# Adafruit_Feather_nRF52840_Sense.net
KiCad netlist of a schematic drawn in EAGLE
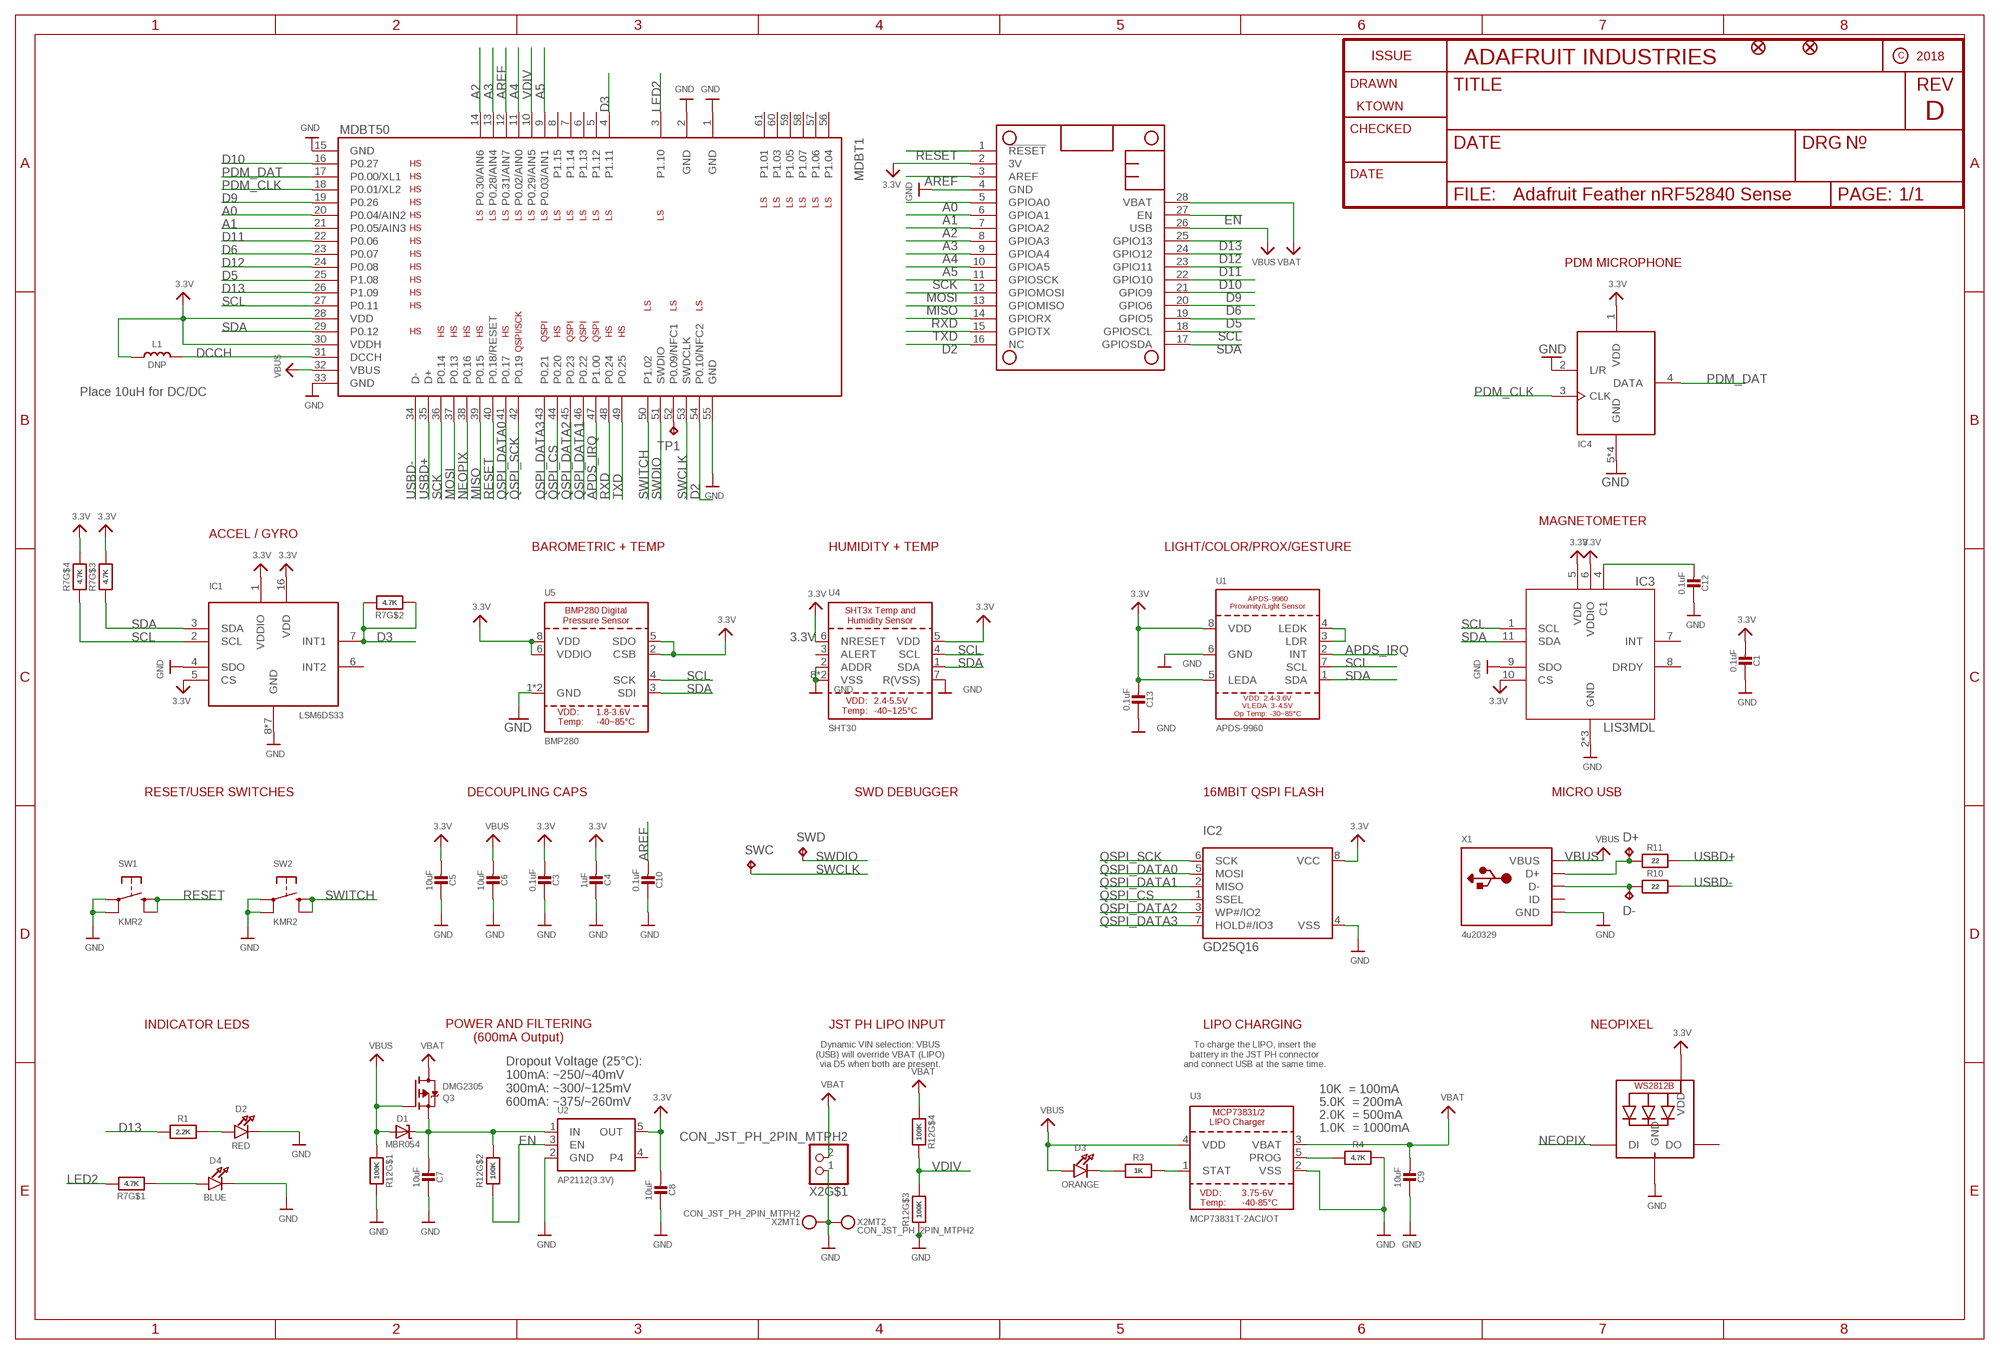
[diagram p0: schematic, sheet 1]

(export (version "E")
  (design (tool "Eeschema 10.0.6"))
  (components
    (comp (ref "C1")
      (value "0.1uF")
      (footprint "eagle-import:0603-NO")
      (libsource (lib "eagle-import") (part "CAP_CERAMIC0603_NO"))
    )
    (comp (ref "C3")
      (value "0.1uF")
      (footprint "eagle-import:0603-NO")
      (libsource (lib "eagle-import") (part "CAP_CERAMIC0603_NO"))
    )
    (comp (ref "C4")
      (value "1uF")
      (footprint "eagle-import:0603-NO")
      (libsource (lib "eagle-import") (part "CAP_CERAMIC0603_NO"))
    )
    (comp (ref "C5")
      (value "10uF")
      (footprint "eagle-import:0805-NO")
      (libsource (lib "eagle-import") (part "CAP_CERAMIC0805-NOOUTLINE"))
    )
    (comp (ref "C6")
      (value "10uF")
      (footprint "eagle-import:0805-NO")
      (libsource (lib "eagle-import") (part "CAP_CERAMIC0805-NOOUTLINE"))
    )
    (comp (ref "C7")
      (value "10uF")
      (footprint "eagle-import:0805-NO")
      (libsource (lib "eagle-import") (part "CAP_CERAMIC0805-NOOUTLINE"))
    )
    (comp (ref "C8")
      (value "10uF")
      (footprint "eagle-import:0805-NO")
      (libsource (lib "eagle-import") (part "CAP_CERAMIC0805-NOOUTLINE"))
    )
    (comp (ref "C9")
      (value "10uF")
      (footprint "eagle-import:0805-NO")
      (libsource (lib "eagle-import") (part "CAP_CERAMIC0805-NOOUTLINE"))
    )
    (comp (ref "C10")
      (value "0.1uF")
      (footprint "eagle-import:0603-NO")
      (libsource (lib "eagle-import") (part "CAP_CERAMIC0603_NO"))
    )
    (comp (ref "C12")
      (value "0.1uF")
      (footprint "eagle-import:0603-NO")
      (libsource (lib "eagle-import") (part "CAP_CERAMIC0603_NO"))
    )
    (comp (ref "C13")
      (value "0.1uF")
      (footprint "eagle-import:0603-NO")
      (libsource (lib "eagle-import") (part "CAP_CERAMIC0603_NO"))
    )
    (comp (ref "D+")
      (value "TPTP10R")
      (footprint "eagle-import:TP10R")
      (libsource (lib "eagle-import") (part "TPTP10R"))
    )
    (comp (ref "D-")
      (value "TPTP10R")
      (footprint "eagle-import:TP10R")
      (libsource (lib "eagle-import") (part "TPTP10R"))
    )
    (comp (ref "D1")
      (value "MBR054")
      (footprint "eagle-import:SOD-123")
      (libsource (lib "eagle-import") (part "DIODE-SCHOTTKYSOD-123"))
    )
    (comp (ref "D2")
      (value "RED")
      (footprint "eagle-import:CHIPLED_0805_NOOUTLINE")
      (libsource (lib "eagle-import") (part "LED0805_NOOUTLINE"))
    )
    (comp (ref "D3")
      (value "ORANGE")
      (footprint "eagle-import:CHIPLED_0805_NOOUTLINE")
      (libsource (lib "eagle-import") (part "LED0805_NOOUTLINE"))
    )
    (comp (ref "D4")
      (value "BLUE")
      (footprint "eagle-import:CHIPLED_0603_NOOUTLINE")
      (libsource (lib "eagle-import") (part "LED0603_NOOUTLINE"))
    )
    (comp (ref "FID1")
      (value "FIDUCIAL_1MM")
      (footprint "eagle-import:FIDUCIAL_1MM")
      (libsource (lib "eagle-import") (part "FIDUCIAL_1MM"))
    )
    (comp (ref "FID2")
      (value "FIDUCIAL_1MM")
      (footprint "eagle-import:FIDUCIAL_1MM")
      (libsource (lib "eagle-import") (part "FIDUCIAL_1MM"))
    )
    (comp (ref "IC1")
      (value "LSM6DS33")
      (footprint "eagle-import:LGA16_3X3MM")
      (libsource (lib "eagle-import") (part "LSM6DS33"))
    )
    (comp (ref "IC2")
      (value "GD25Q16")
      (footprint "eagle-import:USON8")
      (libsource (lib "eagle-import") (part "SPIFLASH_8PINUX"))
    )
    (comp (ref "IC3")
      (value "LIS3MDL")
      (footprint "eagle-import:LGA12_2X2MM")
      (libsource (lib "eagle-import") (part "LIS3MDL"))
    )
    (comp (ref "IC4")
      (value "MIC_PDM")
      (footprint "eagle-import:SPK0415HM4H")
      (libsource (lib "eagle-import") (part "MIC_PDM_SPK0415"))
    )
    (comp (ref "L1")
      (value "DNP")
      (footprint "eagle-import:_0805MP")
      (libsource (lib "eagle-import") (part "INDUCTOR_0805MP"))
    )
    (comp (ref "LED1")
      (value "WS2812B3535")
      (footprint "eagle-import:LED3535")
      (libsource (lib "eagle-import") (part "WS2812B3535"))
    )
    (comp (ref "MDBT1")
      (value "MDBT50")
      (footprint "eagle-import:MDBT50")
      (libsource (lib "eagle-import") (part "MDBT50"))
    )
    (comp (ref "MS1")
      (value "FEATHERWING_NODIM")
      (footprint "eagle-import:FEATHERWING_NODIM")
      (libsource (lib "eagle-import") (part "FEATHERWING_NODIM"))
    )
    (comp (ref "Q3")
      (value "DMG2305")
      (footprint "eagle-import:SOT23-R")
      (libsource (lib "eagle-import") (part "MOSFET-P"))
    )
    (comp (ref "R1")
      (value "2.2K")
      (footprint "eagle-import:0603-NO")
      (libsource (lib "eagle-import") (part "RESISTOR_0603_NOOUT"))
    )
    (comp (ref "R3")
      (value "1K")
      (footprint "eagle-import:0603-NO")
      (libsource (lib "eagle-import") (part "RESISTOR_0603_NOOUT"))
    )
    (comp (ref "R4")
      (value "4.7K")
      (footprint "eagle-import:0603-NO")
      (libsource (lib "eagle-import") (part "RESISTOR_0603_NOOUT"))
    )
    (comp (ref "R7")
      (value "4.7K")
      (footprint "eagle-import:RESPACK_4X0603")
      (libsource (lib "eagle-import") (part "RESISTOR_4PACK"))
    )
    (comp (ref "R10")
      (value "22")
      (footprint "eagle-import:0603-NO")
      (libsource (lib "eagle-import") (part "RESISTOR_0603_NOOUT"))
    )
    (comp (ref "R11")
      (value "22")
      (footprint "eagle-import:0603-NO")
      (libsource (lib "eagle-import") (part "RESISTOR_0603_NOOUT"))
    )
    (comp (ref "R12")
      (value "100K")
      (footprint "eagle-import:RESPACK_4X0603")
      (libsource (lib "eagle-import") (part "RESISTOR_4PACK"))
    )
    (comp (ref "SW1")
      (value "KMR2")
      (footprint "eagle-import:BTN_KMR2_4.6X2.8")
      (libsource (lib "eagle-import") (part "SWITCH_TACT_SMT4.6X2.8"))
    )
    (comp (ref "SW2")
      (value "KMR2")
      (footprint "eagle-import:BTN_KMR2_4.6X2.8")
      (libsource (lib "eagle-import") (part "SWITCH_TACT_SMT4.6X2.8"))
    )
    (comp (ref "SWC")
      (value "TPTP12R")
      (footprint "eagle-import:TP12R")
      (libsource (lib "eagle-import") (part "TPTP12R"))
    )
    (comp (ref "SWD")
      (value "TPTP12R")
      (footprint "eagle-import:TP12R")
      (libsource (lib "eagle-import") (part "TPTP12R"))
    )
    (comp (ref "TP1")
      (value "TPTP10R")
      (footprint "eagle-import:TP10R")
      (libsource (lib "eagle-import") (part "TPTP10R"))
    )
    (comp (ref "U1")
      (value "APDS-9960")
      (footprint "eagle-import:APDS-9960")
      (libsource (lib "eagle-import") (part "APDS-9960"))
    )
    (comp (ref "U2")
      (value "AP2112(3.3V)")
      (footprint "eagle-import:SOT23-5")
      (libsource (lib "eagle-import") (part "VREG_SOT23-5"))
    )
    (comp (ref "U3")
      (value "MCP73831T-2ACI/OT")
      (footprint "eagle-import:SOT23-5")
      (libsource (lib "eagle-import") (part "MCP73831/2"))
    )
    (comp (ref "U4")
      (value "SHT30")
      (footprint "eagle-import:SHT3X")
      (libsource (lib "eagle-import") (part "SHT3X"))
    )
    (comp (ref "U5")
      (value "BMP280")
      (footprint "eagle-import:BMP280")
      (libsource (lib "eagle-import") (part "BMP280"))
    )
    (comp (ref "X1")
      (value "4u20329")
      (footprint "eagle-import:4UCONN_20329_V2")
      (libsource (lib "eagle-import") (part "USB_MICRO_20329_V2"))
    )
    (comp (ref "X2")
      (value "CON_JST_PH_2PIN_MTPH2")
      (footprint "eagle-import:JSTPH2")
      (libsource (lib "eagle-import") (part "CON_JST_PH_2PIN_MTPH2"))
    )
  )
  (nets
    (net (code "1") (name "/A0") (class "Default")
      (node (ref "MDBT1") (pin "20") (pinfunction "P0.04/AIN2_20") (pintype "bidirectional"))
      (node (ref "MS1") (pin "5") (pinfunction "GPIOA0_5") (pintype "bidirectional"))
    )
    (net (code "2") (name "/A1") (class "Default")
      (node (ref "MDBT1") (pin "21") (pinfunction "P0.05/AIN3_21") (pintype "bidirectional"))
      (node (ref "MS1") (pin "6") (pinfunction "GPIOA1_6") (pintype "bidirectional"))
    )
    (net (code "3") (name "/A2") (class "Default")
      (node (ref "MDBT1") (pin "14") (pinfunction "P0.30/AIN6_14") (pintype "bidirectional"))
      (node (ref "MS1") (pin "7") (pinfunction "GPIOA2_7") (pintype "bidirectional"))
    )
    (net (code "4") (name "/A3") (class "Default")
      (node (ref "MDBT1") (pin "13") (pinfunction "P0.28/AIN4_13") (pintype "bidirectional"))
      (node (ref "MS1") (pin "8") (pinfunction "GPIOA3_8") (pintype "bidirectional"))
    )
    (net (code "5") (name "/A4") (class "Default")
      (node (ref "MDBT1") (pin "11") (pinfunction "P0.02/AIN0_11") (pintype "bidirectional"))
      (node (ref "MS1") (pin "9") (pinfunction "GPIOA4_9") (pintype "bidirectional"))
    )
    (net (code "6") (name "/A5") (class "Default")
      (node (ref "MDBT1") (pin "9") (pinfunction "P0.03/AIN1_9") (pintype "bidirectional"))
      (node (ref "MS1") (pin "10") (pinfunction "GPIOA5_10") (pintype "bidirectional"))
    )
    (net (code "7") (name "/APDS_IRQ") (class "Default")
      (node (ref "MDBT1") (pin "47") (pinfunction "P1.00_47") (pintype "bidirectional"))
      (node (ref "U1") (pin "2") (pinfunction "INT_2") (pintype "output"))
    )
    (net (code "8") (name "/AREF") (class "Default")
      (node (ref "C10") (pin "2") (pinfunction "2_2") (pintype "passive"))
      (node (ref "MDBT1") (pin "12") (pinfunction "P0.31/AIN7_12") (pintype "bidirectional"))
      (node (ref "MS1") (pin "3") (pinfunction "AREF_3") (pintype "passive"))
    )
    (net (code "9") (name "/D2") (class "Default")
      (node (ref "MDBT1") (pin "54") (pinfunction "P0.10/NFC2_54") (pintype "bidirectional"))
      (node (ref "MS1") (pin "16") (pinfunction "NC_16") (pintype "passive"))
    )
    (net (code "10") (name "/D3") (class "Default")
      (node (ref "IC1") (pin "7") (pinfunction "INT1_7") (pintype "output"))
      (node (ref "MDBT1") (pin "4") (pinfunction "P1.11_4") (pintype "bidirectional"))
      (node (ref "R7") (pin "2") (pinfunction "1_2") (pintype "passive"))
      (node (ref "R7") (pin "7") (pinfunction "2_7") (pintype "passive"))
    )
    (net (code "11") (name "/D5") (class "Default")
      (node (ref "MDBT1") (pin "25") (pinfunction "P1.08_25") (pintype "bidirectional"))
      (node (ref "MS1") (pin "19") (pinfunction "GPIO5_19") (pintype "bidirectional"))
    )
    (net (code "12") (name "/D6") (class "Default")
      (node (ref "MDBT1") (pin "23") (pinfunction "P0.07_23") (pintype "bidirectional"))
      (node (ref "MS1") (pin "20") (pinfunction "GPIO6_20") (pintype "bidirectional"))
    )
    (net (code "13") (name "/D9") (class "Default")
      (node (ref "MDBT1") (pin "19") (pinfunction "P0.26_19") (pintype "bidirectional"))
      (node (ref "MS1") (pin "21") (pinfunction "GPIO9_21") (pintype "bidirectional"))
    )
    (net (code "14") (name "/D10") (class "Default")
      (node (ref "MDBT1") (pin "16") (pinfunction "P0.27_16") (pintype "bidirectional"))
      (node (ref "MS1") (pin "22") (pinfunction "GPIO10_22") (pintype "bidirectional"))
    )
    (net (code "15") (name "/D11") (class "Default")
      (node (ref "MDBT1") (pin "22") (pinfunction "P0.06_22") (pintype "bidirectional"))
      (node (ref "MS1") (pin "23") (pinfunction "GPIO11_23") (pintype "bidirectional"))
    )
    (net (code "16") (name "/D12") (class "Default")
      (node (ref "MDBT1") (pin "24") (pinfunction "P0.08_24") (pintype "bidirectional"))
      (node (ref "MS1") (pin "24") (pinfunction "GPIO12_24") (pintype "bidirectional"))
    )
    (net (code "17") (name "/D13") (class "Default")
      (node (ref "MDBT1") (pin "26") (pinfunction "P1.09_26") (pintype "bidirectional"))
      (node (ref "MS1") (pin "25") (pinfunction "GPIO13_25") (pintype "bidirectional"))
      (node (ref "R1") (pin "1") (pinfunction "1_1") (pintype "passive"))
    )
    (net (code "18") (name "/DCCH") (class "Default")
      (node (ref "L1") (pin "2") (pinfunction "2_2") (pintype "passive"))
      (node (ref "MDBT1") (pin "31") (pinfunction "DCCH_31") (pintype "bidirectional"))
    )
    (net (code "19") (name "/EN") (class "Default")
      (node (ref "MS1") (pin "27") (pinfunction "EN_27") (pintype "passive"))
      (node (ref "R12") (pin "2") (pinfunction "1_2") (pintype "passive"))
      (node (ref "U2") (pin "3") (pinfunction "EN_3") (pintype "input"))
    )
    (net (code "20") (name "/LED2") (class "Default")
      (node (ref "MDBT1") (pin "3") (pinfunction "P1.10_3") (pintype "bidirectional"))
      (node (ref "R7") (pin "8") (pinfunction "2_8") (pintype "passive"))
    )
    (net (code "21") (name "/MISO") (class "Default")
      (node (ref "MDBT1") (pin "39") (pinfunction "P0.15_39") (pintype "bidirectional"))
      (node (ref "MS1") (pin "13") (pinfunction "GPIOMISO_13") (pintype "bidirectional"))
    )
    (net (code "22") (name "/MOSI") (class "Default")
      (node (ref "MDBT1") (pin "37") (pinfunction "P0.13_37") (pintype "bidirectional"))
      (node (ref "MS1") (pin "12") (pinfunction "GPIOMOSI_12") (pintype "bidirectional"))
    )
    (net (code "23") (name "/NEOPIX") (class "Default")
      (node (ref "LED1") (pin "1") (pinfunction "DI_1") (pintype "input"))
      (node (ref "MDBT1") (pin "38") (pinfunction "P0.16_38") (pintype "bidirectional"))
    )
    (net (code "24") (name "/PDM_CLK") (class "Default")
      (node (ref "IC4") (pin "3") (pinfunction "CLK_3") (pintype "input"))
      (node (ref "MDBT1") (pin "18") (pinfunction "P0.01/XL2_18") (pintype "bidirectional"))
    )
    (net (code "25") (name "/PDM_DAT") (class "Default")
      (node (ref "IC4") (pin "4") (pinfunction "DATA_4") (pintype "bidirectional"))
      (node (ref "MDBT1") (pin "17") (pinfunction "P0.00/XL1_17") (pintype "bidirectional"))
    )
    (net (code "26") (name "/QSPI_CS") (class "Default")
      (node (ref "IC2") (pin "1") (pinfunction "SSEL_1") (pintype "bidirectional"))
      (node (ref "MDBT1") (pin "44") (pinfunction "P0.20_44") (pintype "bidirectional"))
    )
    (net (code "27") (name "/QSPI_DATA0") (class "Default")
      (node (ref "IC2") (pin "5") (pinfunction "MOSI_5") (pintype "bidirectional"))
      (node (ref "MDBT1") (pin "41") (pinfunction "P0.17_41") (pintype "bidirectional"))
    )
    (net (code "28") (name "/QSPI_DATA1") (class "Default")
      (node (ref "IC2") (pin "2") (pinfunction "MISO_2") (pintype "bidirectional"))
      (node (ref "MDBT1") (pin "46") (pinfunction "P0.22_46") (pintype "bidirectional"))
    )
    (net (code "29") (name "/QSPI_DATA2") (class "Default")
      (node (ref "IC2") (pin "3") (pinfunction "WP#/IO2_3") (pintype "bidirectional"))
      (node (ref "MDBT1") (pin "45") (pinfunction "P0.23_45") (pintype "bidirectional"))
    )
    (net (code "30") (name "/QSPI_DATA3") (class "Default")
      (node (ref "IC2") (pin "7") (pinfunction "HOLD#/IO3_7") (pintype "bidirectional"))
      (node (ref "MDBT1") (pin "43") (pinfunction "P0.21_43") (pintype "bidirectional"))
    )
    (net (code "31") (name "/QSPI_SCK") (class "Default")
      (node (ref "IC2") (pin "6") (pinfunction "SCK_6") (pintype "bidirectional"))
      (node (ref "MDBT1") (pin "42") (pinfunction "P0.19_42") (pintype "bidirectional"))
    )
    (net (code "32") (name "/RESET") (class "Default")
      (node (ref "MDBT1") (pin "40") (pinfunction "P0.18/RESET_40") (pintype "bidirectional"))
      (node (ref "MS1") (pin "1") (pinfunction "~{RESET}_1") (pintype "input"))
      (node (ref "SW1") (pin "B") (pinfunction "S_B") (pintype "passive"))
      (node (ref "SW1") (pin "B'") (pinfunction "S1_B'") (pintype "passive"))
    )
    (net (code "33") (name "/RXD") (class "Default")
      (node (ref "MDBT1") (pin "48") (pinfunction "P0.24_48") (pintype "bidirectional"))
      (node (ref "MS1") (pin "14") (pinfunction "GPIORX_14") (pintype "bidirectional"))
    )
    (net (code "34") (name "/SCK") (class "Default")
      (node (ref "MDBT1") (pin "36") (pinfunction "P0.14_36") (pintype "bidirectional"))
      (node (ref "MS1") (pin "11") (pinfunction "GPIOSCK_11") (pintype "bidirectional"))
    )
    (net (code "35") (name "/SCL") (class "Default")
      (node (ref "IC1") (pin "2") (pinfunction "SCL_2") (pintype "bidirectional"))
      (node (ref "IC3") (pin "1") (pinfunction "SCL_1") (pintype "input"))
      (node (ref "MDBT1") (pin "27") (pinfunction "P0.11_27") (pintype "bidirectional"))
      (node (ref "MS1") (pin "18") (pinfunction "GPIOSCL_18") (pintype "bidirectional"))
      (node (ref "R7") (pin "4") (pinfunction "1_4") (pintype "passive"))
      (node (ref "U1") (pin "7") (pinfunction "SCL_7") (pintype "input"))
      (node (ref "U4") (pin "4") (pinfunction "SCL_4") (pintype "bidirectional"))
      (node (ref "U5") (pin "4") (pinfunction "SCK_4") (pintype "input"))
    )
    (net (code "36") (name "/SDA") (class "Default")
      (node (ref "IC1") (pin "3") (pinfunction "SDA_3") (pintype "bidirectional"))
      (node (ref "IC3") (pin "11") (pinfunction "SDA_11") (pintype "bidirectional"))
      (node (ref "MDBT1") (pin "29") (pinfunction "P0.12_29") (pintype "bidirectional"))
      (node (ref "MS1") (pin "17") (pinfunction "GPIOSDA_17") (pintype "bidirectional"))
      (node (ref "R7") (pin "3") (pinfunction "1_3") (pintype "passive"))
      (node (ref "U1") (pin "1") (pinfunction "SDA_1") (pintype "bidirectional"))
      (node (ref "U4") (pin "1") (pinfunction "SDA_1") (pintype "bidirectional"))
      (node (ref "U5") (pin "3") (pinfunction "SDI_3") (pintype "input"))
    )
    (net (code "37") (name "/SWCLK") (class "Default")
      (node (ref "MDBT1") (pin "53") (pinfunction "SWDCLK_53") (pintype "bidirectional"))
      (node (ref "SWC") (pin "TP") (pinfunction "TP_TP") (pintype "input"))
    )
    (net (code "38") (name "/SWDIO") (class "Default")
      (node (ref "MDBT1") (pin "51") (pinfunction "SWDIO_51") (pintype "bidirectional"))
      (node (ref "SWD") (pin "TP") (pinfunction "TP_TP") (pintype "input"))
    )
    (net (code "39") (name "/SWITCH") (class "Default")
      (node (ref "MDBT1") (pin "50") (pinfunction "P1.02_50") (pintype "bidirectional"))
      (node (ref "SW2") (pin "B") (pinfunction "S_B") (pintype "passive"))
      (node (ref "SW2") (pin "B'") (pinfunction "S1_B'") (pintype "passive"))
    )
    (net (code "40") (name "/TXD") (class "Default")
      (node (ref "MDBT1") (pin "49") (pinfunction "P0.25_49") (pintype "bidirectional"))
      (node (ref "MS1") (pin "15") (pinfunction "GPIOTX_15") (pintype "bidirectional"))
    )
    (net (code "41") (name "/USBD+") (class "Default")
      (node (ref "MDBT1") (pin "35") (pinfunction "D+_35") (pintype "bidirectional"))
      (node (ref "R11") (pin "2") (pinfunction "2_2") (pintype "passive"))
    )
    (net (code "42") (name "/USBD-") (class "Default")
      (node (ref "MDBT1") (pin "34") (pinfunction "D-_34") (pintype "bidirectional"))
      (node (ref "R10") (pin "2") (pinfunction "2_2") (pintype "passive"))
    )
    (net (code "43") (name "/VDIV") (class "Default")
      (node (ref "MDBT1") (pin "10") (pinfunction "P0.29/AIN5_10") (pintype "bidirectional"))
      (node (ref "R12") (pin "5") (pinfunction "2_5") (pintype "passive"))
      (node (ref "R12") (pin "6") (pinfunction "2_6") (pintype "passive"))
    )
    (net (code "44") (name "3.3V") (class "Default")
      (node (ref "C1") (pin "2") (pinfunction "2_2") (pintype "passive"))
      (node (ref "C13") (pin "2") (pinfunction "2_2") (pintype "passive"))
      (node (ref "C3") (pin "2") (pinfunction "2_2") (pintype "passive"))
      (node (ref "C4") (pin "2") (pinfunction "2_2") (pintype "passive"))
      (node (ref "C5") (pin "2") (pinfunction "2_2") (pintype "passive"))
      (node (ref "C8") (pin "2") (pinfunction "2_2") (pintype "passive"))
      (node (ref "IC1") (pin "1") (pinfunction "VDDIO_1") (pintype "power_in"))
      (node (ref "IC1") (pin "16") (pinfunction "VDD_16") (pintype "power_in"))
      (node (ref "IC1") (pin "5") (pinfunction "CS_5") (pintype "input"))
      (node (ref "IC2") (pin "8") (pinfunction "VCC_8") (pintype "bidirectional"))
      (node (ref "IC3") (pin "10") (pinfunction "CS_10") (pintype "input"))
      (node (ref "IC3") (pin "5") (pinfunction "VDD_5") (pintype "power_in"))
      (node (ref "IC3") (pin "6") (pinfunction "VDDIO_6") (pintype "power_in"))
      (node (ref "IC4") (pin "1") (pinfunction "VDD_1") (pintype "power_in"))
      (node (ref "L1") (pin "1") (pinfunction "1_1") (pintype "passive"))
      (node (ref "LED1") (pin "2") (pinfunction "VDD_2") (pintype "power_in"))
      (node (ref "MDBT1") (pin "28") (pinfunction "VDD_28") (pintype "bidirectional"))
      (node (ref "MDBT1") (pin "30") (pinfunction "VDDH_30") (pintype "bidirectional"))
      (node (ref "MS1") (pin "2") (pinfunction "3V_2") (pintype "power_in"))
      (node (ref "R7") (pin "5") (pinfunction "2_5") (pintype "passive"))
      (node (ref "R7") (pin "6") (pinfunction "2_6") (pintype "passive"))
      (node (ref "U1") (pin "5") (pinfunction "LEDA_5") (pintype "power_in"))
      (node (ref "U1") (pin "8") (pinfunction "VDD_8") (pintype "power_in"))
      (node (ref "U2") (pin "5") (pinfunction "OUT_5") (pintype "power_in"))
      (node (ref "U4") (pin "5") (pinfunction "VDD_5") (pintype "power_in"))
      (node (ref "U4") (pin "6") (pinfunction "NRESET_6") (pintype "bidirectional"))
      (node (ref "U5") (pin "2") (pinfunction "CSB_2") (pintype "input"))
      (node (ref "U5") (pin "5") (pinfunction "SDO_5") (pintype "output"))
      (node (ref "U5") (pin "6") (pinfunction "VDDIO_6") (pintype "power_in"))
      (node (ref "U5") (pin "8") (pinfunction "VDD_8") (pintype "power_in"))
    )
    (net (code "45") (name "GND") (class "Default")
      (node (ref "C1") (pin "1") (pinfunction "1_1") (pintype "passive"))
      (node (ref "C10") (pin "1") (pinfunction "1_1") (pintype "passive"))
      (node (ref "C12") (pin "1") (pinfunction "1_1") (pintype "passive"))
      (node (ref "C13") (pin "1") (pinfunction "1_1") (pintype "passive"))
      (node (ref "C3") (pin "1") (pinfunction "1_1") (pintype "passive"))
      (node (ref "C4") (pin "1") (pinfunction "1_1") (pintype "passive"))
      (node (ref "C5") (pin "1") (pinfunction "1_1") (pintype "passive"))
      (node (ref "C6") (pin "1") (pinfunction "1_1") (pintype "passive"))
      (node (ref "C7") (pin "1") (pinfunction "1_1") (pintype "passive"))
      (node (ref "C8") (pin "1") (pinfunction "1_1") (pintype "passive"))
      (node (ref "C9") (pin "1") (pinfunction "1_1") (pintype "passive"))
      (node (ref "D2") (pin "C") (pinfunction "C_C") (pintype "passive"))
      (node (ref "D4") (pin "C") (pinfunction "C_C") (pintype "passive"))
      (node (ref "IC1") (pin "10") (pinfunction "GND_10") (pintype "power_in"))
      (node (ref "IC1") (pin "11") (pinfunction "GND_11") (pintype "power_in"))
      (node (ref "IC1") (pin "12") (pinfunction "GND_12") (pintype "power_in"))
      (node (ref "IC1") (pin "13") (pinfunction "GND_13") (pintype "power_in"))
      (node (ref "IC1") (pin "15") (pinfunction "GND_15") (pintype "power_in"))
      (node (ref "IC1") (pin "4") (pinfunction "SDO_4") (pintype "bidirectional"))
      (node (ref "IC1") (pin "8") (pinfunction "GND_8") (pintype "power_in"))
      (node (ref "IC1") (pin "9") (pinfunction "GND_9") (pintype "power_in"))
      (node (ref "IC2") (pin "4") (pinfunction "VSS_4") (pintype "bidirectional"))
      (node (ref "IC3") (pin "12") (pinfunction "GND_12") (pintype "power_in"))
      (node (ref "IC3") (pin "2") (pinfunction "GND_2") (pintype "power_in"))
      (node (ref "IC3") (pin "3") (pinfunction "GND_3") (pintype "power_in"))
      (node (ref "IC3") (pin "9") (pinfunction "SDO_9") (pintype "bidirectional"))
      (node (ref "IC4") (pin "2") (pinfunction "L/R_2") (pintype "input"))
      (node (ref "IC4") (pin "5") (pinfunction "GND_5") (pintype "power_in"))
      (node (ref "IC4") (pin "6") (pinfunction "GND_6") (pintype "power_in"))
      (node (ref "IC4") (pin "7") (pinfunction "GND_7") (pintype "power_in"))
      (node (ref "IC4") (pin "8") (pinfunction "GND_8") (pintype "power_in"))
      (node (ref "LED1") (pin "4") (pinfunction "GND_4") (pintype "power_in"))
      (node (ref "MDBT1") (pin "1") (pinfunction "GND_1") (pintype "bidirectional"))
      (node (ref "MDBT1") (pin "15") (pinfunction "GND_15") (pintype "bidirectional"))
      (node (ref "MDBT1") (pin "2") (pinfunction "GND_2") (pintype "bidirectional"))
      (node (ref "MDBT1") (pin "33") (pinfunction "GND_33") (pintype "bidirectional"))
      (node (ref "MDBT1") (pin "55") (pinfunction "GND_55") (pintype "bidirectional"))
      (node (ref "MS1") (pin "4") (pinfunction "GND_4") (pintype "power_in"))
      (node (ref "R12") (pin "3") (pinfunction "1_3") (pintype "passive"))
      (node (ref "R12") (pin "8") (pinfunction "2_8") (pintype "passive"))
      (node (ref "R4") (pin "2") (pinfunction "2_2") (pintype "passive"))
      (node (ref "SW1") (pin "A") (pinfunction "P_A") (pintype "passive"))
      (node (ref "SW1") (pin "A'") (pinfunction "P1_A'") (pintype "passive"))
      (node (ref "SW2") (pin "A") (pinfunction "P_A") (pintype "passive"))
      (node (ref "SW2") (pin "A'") (pinfunction "P1_A'") (pintype "passive"))
      (node (ref "U1") (pin "6") (pinfunction "GND_6") (pintype "power_in"))
      (node (ref "U2") (pin "2") (pinfunction "GND_2") (pintype "power_in"))
      (node (ref "U3") (pin "2") (pinfunction "VSS_2") (pintype "power_in"))
      (node (ref "U4") (pin "2") (pinfunction "ADDR_2") (pintype "bidirectional"))
      (node (ref "U4") (pin "7") (pinfunction "R(VSS)_7") (pintype "bidirectional"))
      (node (ref "U4") (pin "8") (pinfunction "VSS_8") (pintype "power_in"))
      (node (ref "U4") (pin "THERMAL") (pinfunction "VSS_THERMAL") (pintype "power_in"))
      (node (ref "U5") (pin "1") (pinfunction "GND_1") (pintype "power_in"))
      (node (ref "U5") (pin "7") (pinfunction "GND_7") (pintype "power_in"))
      (node (ref "X1") (pin "BASE@1") (pinfunction "GND_BASE@1") (pintype "power_in"))
      (node (ref "X1") (pin "BASE@2") (pinfunction "GND_BASE@2") (pintype "power_in"))
      (node (ref "X1") (pin "GND") (pinfunction "GND_GND") (pintype "power_in"))
      (node (ref "X1") (pin "SPRT@1") (pinfunction "GND_SPRT@1") (pintype "power_in"))
      (node (ref "X1") (pin "SPRT@2") (pinfunction "GND_SPRT@2") (pintype "power_in"))
      (node (ref "X1") (pin "SPRT@3") (pinfunction "GND_SPRT@3") (pintype "power_in"))
      (node (ref "X1") (pin "SPRT@4") (pinfunction "GND_SPRT@4") (pintype "power_in"))
      (node (ref "X2") (pin "1") (pinfunction "1_1") (pintype "passive"))
      (node (ref "X2") (pin "NC1") (pinfunction "P$1_NC1") (pintype "bidirectional"))
      (node (ref "X2") (pin "NC2") (pinfunction "P$1_NC2") (pintype "bidirectional"))
    )
    (net (code "46") (name "Net-(D+-PadTP)") (class "Default")
      (node (ref "D+") (pin "TP") (pinfunction "TP_TP") (pintype "input"))
      (node (ref "R11") (pin "1") (pinfunction "1_1") (pintype "passive"))
      (node (ref "X1") (pin "D+") (pinfunction "D+_D+") (pintype "bidirectional"))
    )
    (net (code "47") (name "Net-(D--PadTP)") (class "Default")
      (node (ref "D-") (pin "TP") (pinfunction "TP_TP") (pintype "input"))
      (node (ref "R10") (pin "1") (pinfunction "1_1") (pintype "passive"))
      (node (ref "X1") (pin "D-") (pinfunction "D-_D-") (pintype "bidirectional"))
    )
    (net (code "48") (name "Net-(D2-PadA)") (class "Default")
      (node (ref "D2") (pin "A") (pinfunction "A_A") (pintype "passive"))
      (node (ref "R1") (pin "2") (pinfunction "2_2") (pintype "passive"))
    )
    (net (code "49") (name "Net-(D3-PadC)") (class "Default")
      (node (ref "D3") (pin "C") (pinfunction "C_C") (pintype "passive"))
      (node (ref "R3") (pin "1") (pinfunction "1_1") (pintype "passive"))
    )
    (net (code "50") (name "Net-(D4-PadA)") (class "Default")
      (node (ref "D4") (pin "A") (pinfunction "A_A") (pintype "passive"))
      (node (ref "R7") (pin "1") (pinfunction "1_1") (pintype "passive"))
    )
    (net (code "51") (name "Net-(IC3-C1)") (class "Default")
      (node (ref "C12") (pin "2") (pinfunction "2_2") (pintype "passive"))
      (node (ref "IC3") (pin "4") (pinfunction "C1_4") (pintype "input"))
    )
    (net (code "52") (name "Net-(MDBT1-P0.09{slash}NFC1)") (class "Default")
      (node (ref "MDBT1") (pin "52") (pinfunction "P0.09/NFC1_52") (pintype "bidirectional"))
      (node (ref "TP1") (pin "TP") (pinfunction "TP_TP") (pintype "input"))
    )
    (net (code "53") (name "Net-(Q3-S)") (class "Default")
      (node (ref "C7") (pin "2") (pinfunction "2_2") (pintype "passive"))
      (node (ref "D1") (pin "C") (pinfunction "C_C") (pintype "passive"))
      (node (ref "Q3") (pin "2") (pinfunction "S_2") (pintype "passive"))
      (node (ref "R12") (pin "7") (pinfunction "2_7") (pintype "passive"))
      (node (ref "U2") (pin "1") (pinfunction "IN_1") (pintype "power_in"))
    )
    (net (code "54") (name "Net-(U1-LDR)") (class "Default")
      (node (ref "U1") (pin "3") (pinfunction "LDR_3") (pintype "bidirectional"))
      (node (ref "U1") (pin "4") (pinfunction "LEDK_4") (pintype "bidirectional"))
    )
    (net (code "55") (name "Net-(U3-PROG)") (class "Default")
      (node (ref "R4") (pin "1") (pinfunction "1_1") (pintype "passive"))
      (node (ref "U3") (pin "5") (pinfunction "PROG_5") (pintype "input"))
    )
    (net (code "56") (name "Net-(U3-STAT)") (class "Default")
      (node (ref "R3") (pin "2") (pinfunction "2_2") (pintype "passive"))
      (node (ref "U3") (pin "1") (pinfunction "STAT_1") (pintype "output"))
    )
    (net (code "57") (name "VBAT") (class "Default")
      (node (ref "C9") (pin "2") (pinfunction "2_2") (pintype "passive"))
      (node (ref "MS1") (pin "28") (pinfunction "VBAT_28") (pintype "power_in"))
      (node (ref "Q3") (pin "3") (pinfunction "D_3") (pintype "passive"))
      (node (ref "R12") (pin "4") (pinfunction "1_4") (pintype "passive"))
      (node (ref "U3") (pin "3") (pinfunction "VBAT_3") (pintype "power_in"))
      (node (ref "X2") (pin "2") (pinfunction "2_2") (pintype "passive"))
    )
    (net (code "58") (name "VBUS") (class "Default")
      (node (ref "C6") (pin "2") (pinfunction "2_2") (pintype "passive"))
      (node (ref "D1") (pin "A") (pinfunction "A_A") (pintype "passive"))
      (node (ref "D3") (pin "A") (pinfunction "A_A") (pintype "passive"))
      (node (ref "MDBT1") (pin "32") (pinfunction "VBUS_32") (pintype "bidirectional"))
      (node (ref "MS1") (pin "26") (pinfunction "USB_26") (pintype "power_in"))
      (node (ref "Q3") (pin "1") (pinfunction "G_1") (pintype "passive"))
      (node (ref "R12") (pin "1") (pinfunction "1_1") (pintype "passive"))
      (node (ref "U3") (pin "4") (pinfunction "VDD_4") (pintype "power_in"))
      (node (ref "X1") (pin "VBUS") (pinfunction "VBUS_VBUS") (pintype "power_in"))
    )
    (net (code "59") (name "unconnected-(IC1-INT2-Pad6)") (class "Default")
      (node (ref "IC1") (pin "6") (pinfunction "INT2_6") (pintype "output"))
    )
    (net (code "60") (name "unconnected-(IC3-DRDY-Pad8)") (class "Default")
      (node (ref "IC3") (pin "8") (pinfunction "DRDY_8") (pintype "output"))
    )
    (net (code "61") (name "unconnected-(IC3-INT-Pad7)") (class "Default")
      (node (ref "IC3") (pin "7") (pinfunction "INT_7") (pintype "output"))
    )
    (net (code "62") (name "unconnected-(LED1-DO-Pad3)") (class "Default")
      (node (ref "LED1") (pin "3") (pinfunction "DO_3") (pintype "output"))
    )
    (net (code "63") (name "unconnected-(MDBT1-P1.01-Pad61)") (class "Default")
      (node (ref "MDBT1") (pin "61") (pinfunction "P1.01_61") (pintype "bidirectional"))
    )
    (net (code "64") (name "unconnected-(MDBT1-P1.03-Pad60)") (class "Default")
      (node (ref "MDBT1") (pin "60") (pinfunction "P1.03_60") (pintype "bidirectional"))
    )
    (net (code "65") (name "unconnected-(MDBT1-P1.04-Pad56)") (class "Default")
      (node (ref "MDBT1") (pin "56") (pinfunction "P1.04_56") (pintype "bidirectional"))
    )
    (net (code "66") (name "unconnected-(MDBT1-P1.05-Pad59)") (class "Default")
      (node (ref "MDBT1") (pin "59") (pinfunction "P1.05_59") (pintype "bidirectional"))
    )
    (net (code "67") (name "unconnected-(MDBT1-P1.06-Pad57)") (class "Default")
      (node (ref "MDBT1") (pin "57") (pinfunction "P1.06_57") (pintype "bidirectional"))
    )
    (net (code "68") (name "unconnected-(MDBT1-P1.07-Pad58)") (class "Default")
      (node (ref "MDBT1") (pin "58") (pinfunction "P1.07_58") (pintype "bidirectional"))
    )
    (net (code "69") (name "unconnected-(MDBT1-P1.12-Pad5)") (class "Default")
      (node (ref "MDBT1") (pin "5") (pinfunction "P1.12_5") (pintype "bidirectional"))
    )
    (net (code "70") (name "unconnected-(MDBT1-P1.13-Pad6)") (class "Default")
      (node (ref "MDBT1") (pin "6") (pinfunction "P1.13_6") (pintype "bidirectional"))
    )
    (net (code "71") (name "unconnected-(MDBT1-P1.14-Pad7)") (class "Default")
      (node (ref "MDBT1") (pin "7") (pinfunction "P1.14_7") (pintype "bidirectional"))
    )
    (net (code "72") (name "unconnected-(MDBT1-P1.15-Pad8)") (class "Default")
      (node (ref "MDBT1") (pin "8") (pinfunction "P1.15_8") (pintype "bidirectional"))
    )
    (net (code "73") (name "unconnected-(U2-P4-Pad4)") (class "Default")
      (node (ref "U2") (pin "4") (pinfunction "P4_4") (pintype "bidirectional"))
    )
    (net (code "74") (name "unconnected-(U4-ALERT-Pad3)") (class "Default")
      (node (ref "U4") (pin "3") (pinfunction "ALERT_3") (pintype "bidirectional"))
    )
    (net (code "75") (name "unconnected-(X1-PadID)") (class "Default")
      (node (ref "X1") (pin "ID") (pinfunction "ID_ID") (pintype "bidirectional"))
    )
  )
)
